# Perifericos_Schematic.net
KiCad netlist of a schematic drawn in Altium Designer
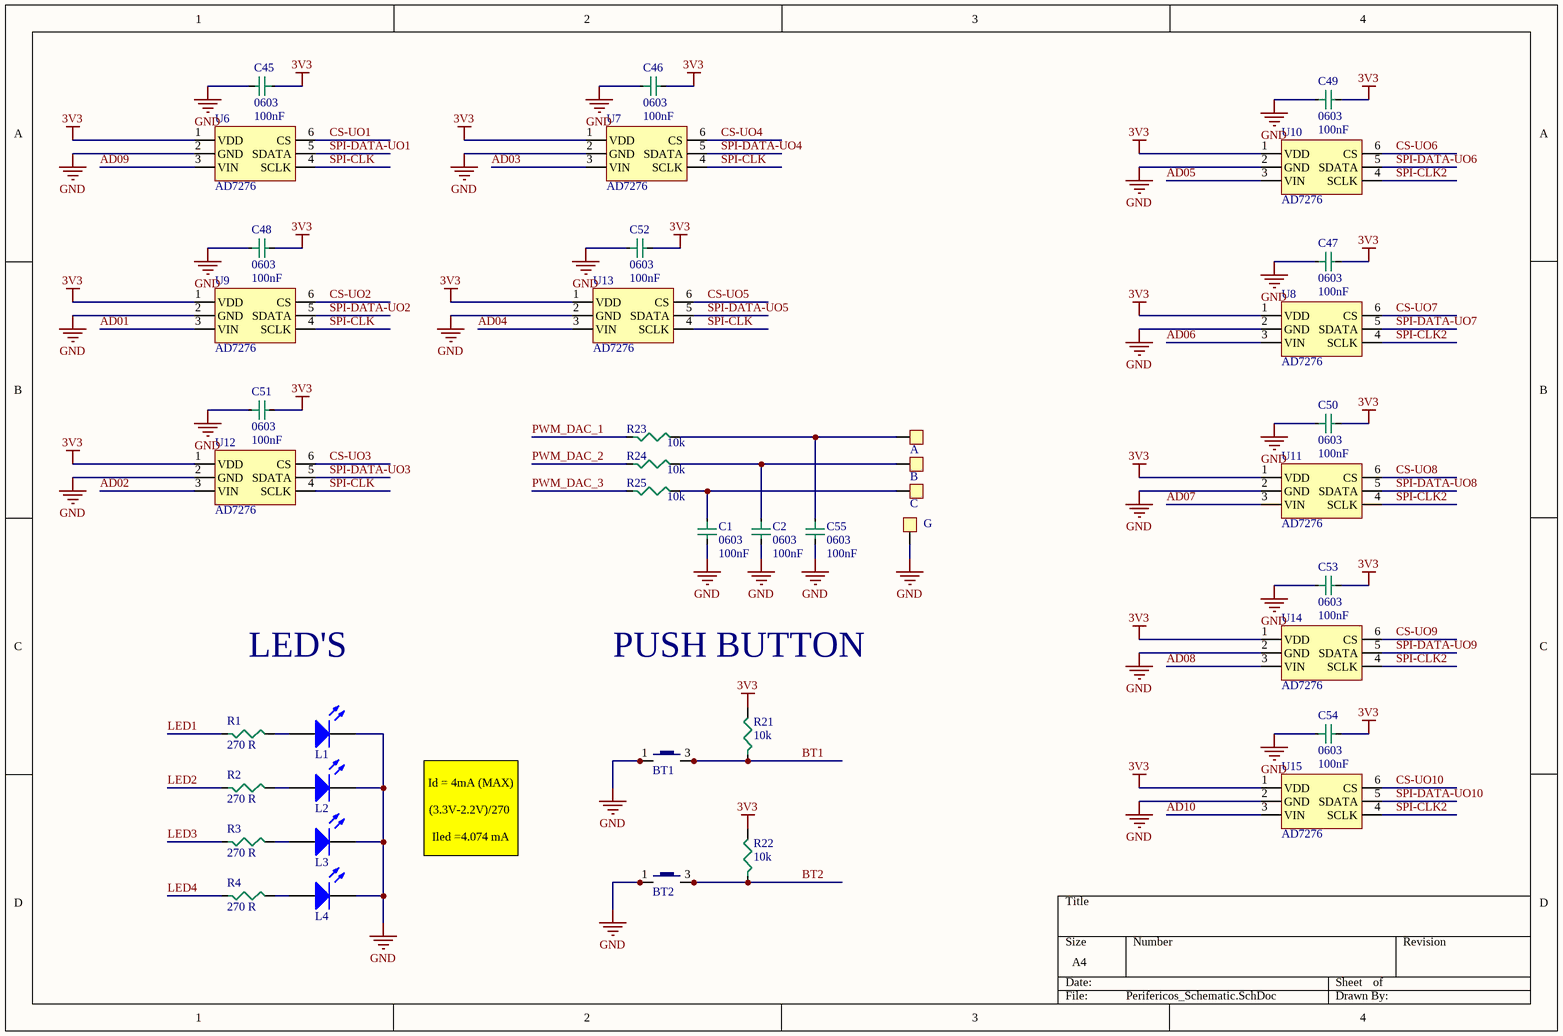
[diagram p0: Perifericos_Schematic.SchDoc]

(export (version "E")
  (design (tool "Eeschema 10.0.6"))
  (components
    (comp (ref "A")
      (value "TEST POINT PC MINI .040\"D, 0.010\" x 0.020\" (0.25mm x 0.51mm)")
      (footprint "PC test RED")
      (libsource (lib "") (part "Test Point Keystone_1"))
    )
    (comp (ref "B")
      (value "TEST POINT PC MINI .040\"D, 0.010\" x 0.020\" (0.25mm x 0.51mm)")
      (footprint "PC test GREEN")
      (libsource (lib "") (part "Test Point Keystone_1"))
    )
    (comp (ref "BT1")
      (value "BOTAO SMD_MENOR")
      (footprint "BOTAO SMD - MENOR")
      (description "SWITCH TACTILE SPST-NO 0.05A 32V")
      (libsource (lib "Schlib1") (part "BOTAO SMD_MENOR"))
    )
    (comp (ref "BT2")
      (value "BOTAO SMD_MENOR")
      (footprint "BOTAO SMD - MENOR")
      (description "SWITCH TACTILE SPST-NO 0.05A 32V")
      (libsource (lib "Schlib1") (part "BOTAO SMD_MENOR"))
    )
    (comp (ref "C")
      (value "TEST POINT PC MINI .040\"D, 0.010\" x 0.020\" (0.25mm x 0.51mm)")
      (footprint "PC test BLUE")
      (libsource (lib "") (part "Test Point Keystone_1"))
    )
    (comp (ref "C1")
      (value "0603")
      (footprint "0603C")
      (description "Capacitor SMD 0603")
      (fields (field (name "ALTIUM_VALUE") "100nF"))
      (libsource (lib "RLC_Integrated_Library") (part "Capacitor SMD 0603"))
    )
    (comp (ref "C2")
      (value "0603")
      (footprint "0603C")
      (description "Capacitor SMD 0603")
      (fields (field (name "ALTIUM_VALUE") "100nF"))
      (libsource (lib "RLC_Integrated_Library") (part "Capacitor SMD 0603"))
    )
    (comp (ref "C45")
      (value "0603")
      (footprint "0603C")
      (description "Capacitor SMD 0603")
      (fields (field (name "ALTIUM_VALUE") "100nF"))
      (libsource (lib "RLC_Integrated_Library") (part "Capacitor SMD 0603"))
    )
    (comp (ref "C46")
      (value "0603")
      (footprint "0603C")
      (description "Capacitor SMD 0603")
      (fields (field (name "ALTIUM_VALUE") "100nF"))
      (libsource (lib "RLC_Integrated_Library") (part "Capacitor SMD 0603"))
    )
    (comp (ref "C47")
      (value "0603")
      (footprint "0603C")
      (description "Capacitor SMD 0603")
      (fields (field (name "ALTIUM_VALUE") "100nF"))
      (libsource (lib "RLC_Integrated_Library") (part "Capacitor SMD 0603"))
    )
    (comp (ref "C48")
      (value "0603")
      (footprint "0603C")
      (description "Capacitor SMD 0603")
      (fields (field (name "ALTIUM_VALUE") "100nF"))
      (libsource (lib "RLC_Integrated_Library") (part "Capacitor SMD 0603"))
    )
    (comp (ref "C49")
      (value "0603")
      (footprint "0603C")
      (description "Capacitor SMD 0603")
      (fields (field (name "ALTIUM_VALUE") "100nF"))
      (libsource (lib "RLC_Integrated_Library") (part "Capacitor SMD 0603"))
    )
    (comp (ref "C50")
      (value "0603")
      (footprint "0603C")
      (description "Capacitor SMD 0603")
      (fields (field (name "ALTIUM_VALUE") "100nF"))
      (libsource (lib "RLC_Integrated_Library") (part "Capacitor SMD 0603"))
    )
    (comp (ref "C51")
      (value "0603")
      (footprint "0603C")
      (description "Capacitor SMD 0603")
      (fields (field (name "ALTIUM_VALUE") "100nF"))
      (libsource (lib "RLC_Integrated_Library") (part "Capacitor SMD 0603"))
    )
    (comp (ref "C52")
      (value "0603")
      (footprint "0603C")
      (description "Capacitor SMD 0603")
      (fields (field (name "ALTIUM_VALUE") "100nF"))
      (libsource (lib "RLC_Integrated_Library") (part "Capacitor SMD 0603"))
    )
    (comp (ref "C53")
      (value "0603")
      (footprint "0603C")
      (description "Capacitor SMD 0603")
      (fields (field (name "ALTIUM_VALUE") "100nF"))
      (libsource (lib "RLC_Integrated_Library") (part "Capacitor SMD 0603"))
    )
    (comp (ref "C54")
      (value "0603")
      (footprint "0603C")
      (description "Capacitor SMD 0603")
      (fields (field (name "ALTIUM_VALUE") "100nF"))
      (libsource (lib "RLC_Integrated_Library") (part "Capacitor SMD 0603"))
    )
    (comp (ref "C55")
      (value "0603")
      (footprint "0603C")
      (description "Capacitor SMD 0603")
      (fields (field (name "ALTIUM_VALUE") "100nF"))
      (libsource (lib "RLC_Integrated_Library") (part "Capacitor SMD 0603"))
    )
    (comp (ref "G")
      (value "TEST POINT PC MINI .040\"D, 0.010\" x 0.020\" (0.25mm x 0.51mm)")
      (footprint "PC test BLACK")
      (libsource (lib "Miscellaneous_Connectors_Integrated_Library") (part "Test Point Keystone"))
    )
    (comp (ref "L1")
      (value "LED 0603")
      (footprint "LED SMD 0603")
      (description "Typical INFRARED GaAs LED")
      (fields (field (name "PUBLISHER") "Altium Limited"))
      (libsource (lib "Diodo_Transistor_Integrated_Library") (part "LED 0603 SMD"))
    )
    (comp (ref "L2")
      (value "LED 0805")
      (footprint "LED SMD 0603")
      (description "Typical INFRARED GaAs LED")
      (fields (field (name "PUBLISHER") "Altium Limited"))
      (libsource (lib "Diodo_Transistor_Integrated_Library") (part "LED 0603 SMD"))
    )
    (comp (ref "L3")
      (value "LED 0805")
      (footprint "LED SMD 0603")
      (description "Typical INFRARED GaAs LED")
      (fields (field (name "PUBLISHER") "Altium Limited"))
      (libsource (lib "Diodo_Transistor_Integrated_Library") (part "LED 0603 SMD"))
    )
    (comp (ref "L4")
      (value "LED 0805")
      (footprint "LED SMD 0603")
      (description "Typical INFRARED GaAs LED")
      (fields (field (name "PUBLISHER") "Altium Limited"))
      (libsource (lib "Diodo_Transistor_Integrated_Library") (part "LED 0603 SMD"))
    )
    (comp (ref "R1")
      (value "270 R")
      (footprint "0603")
      (description "Resistor SMD 0603 1/10 W")
      (fields (field (name "Comment") "0603"))
      (libsource (lib "RLC_Integrated_Library") (part "Resistor SMD 0603 1/10 W"))
    )
    (comp (ref "R2")
      (value "270 R")
      (footprint "0603")
      (description "Resistor SMD 0603 1/10 W")
      (fields (field (name "Comment") "0805"))
      (libsource (lib "RLC_Integrated_Library") (part "Resistor SMD 0603 1/10 W"))
    )
    (comp (ref "R3")
      (value "270 R")
      (footprint "0603")
      (description "Resistor SMD 0603 1/10 W")
      (fields (field (name "Comment") "0805"))
      (libsource (lib "RLC_Integrated_Library") (part "Resistor SMD 0603 1/10 W"))
    )
    (comp (ref "R4")
      (value "270 R")
      (footprint "0603")
      (description "Resistor SMD 0603 1/10 W")
      (fields (field (name "Comment") "0805"))
      (libsource (lib "RLC_Integrated_Library") (part "Resistor SMD 0603 1/10 W"))
    )
    (comp (ref "R21")
      (value "10k")
      (footprint "0603")
      (description "Resistor SMD 0603 1/10 W")
      (fields (field (name "Comment") "0603"))
      (libsource (lib "RLC_Integrated_Library") (part "Resistor SMD 0603 1/10 W"))
    )
    (comp (ref "R22")
      (value "10k")
      (footprint "0603")
      (description "Resistor SMD 0603 1/10 W")
      (fields (field (name "Comment") "0603"))
      (libsource (lib "RLC_Integrated_Library") (part "Resistor SMD 0603 1/10 W"))
    )
    (comp (ref "R23")
      (value "10k")
      (footprint "0603")
      (description "Resistor SMD 0603 1/10 W")
      (fields (field (name "Comment") "0603"))
      (libsource (lib "RLC_Integrated_Library") (part "Resistor SMD 0603 1/10 W"))
    )
    (comp (ref "R24")
      (value "10k")
      (footprint "0603")
      (description "Resistor SMD 0603 1/10 W")
      (fields (field (name "Comment") "0603"))
      (libsource (lib "RLC_Integrated_Library") (part "Resistor SMD 0603 1/10 W"))
    )
    (comp (ref "R25")
      (value "10k")
      (footprint "0603")
      (description "Resistor SMD 0603 1/10 W")
      (fields (field (name "Comment") "0603"))
      (libsource (lib "RLC_Integrated_Library") (part "Resistor SMD 0603 1/10 W"))
    )
    (comp (ref "U6")
      (value "AD7276")
      (footprint "SOT23-6")
      (description "IC ADC 12BIT 3MSPS 6TSOT")
      (libsource (lib "Schlib1") (part "AD7276AUJZ-500RL7"))
    )
    (comp (ref "U7")
      (value "AD7276")
      (footprint "SOT23-6")
      (description "IC ADC 12BIT 3MSPS 6TSOT")
      (libsource (lib "Schlib1") (part "AD7276AUJZ-500RL7"))
    )
    (comp (ref "U8")
      (value "AD7276")
      (footprint "SOT23-6")
      (description "IC ADC 12BIT 3MSPS 6TSOT")
      (libsource (lib "Schlib1") (part "AD7276AUJZ-500RL7"))
    )
    (comp (ref "U9")
      (value "AD7276")
      (footprint "SOT23-6")
      (description "IC ADC 12BIT 3MSPS 6TSOT")
      (libsource (lib "Schlib1") (part "AD7276AUJZ-500RL7"))
    )
    (comp (ref "U10")
      (value "AD7276")
      (footprint "SOT23-6")
      (description "IC ADC 12BIT 3MSPS 6TSOT")
      (libsource (lib "Schlib1") (part "AD7276AUJZ-500RL7"))
    )
    (comp (ref "U11")
      (value "AD7276")
      (footprint "SOT23-6")
      (description "IC ADC 12BIT 3MSPS 6TSOT")
      (libsource (lib "Schlib1") (part "AD7276AUJZ-500RL7"))
    )
    (comp (ref "U12")
      (value "AD7276")
      (footprint "SOT23-6")
      (description "IC ADC 12BIT 3MSPS 6TSOT")
      (libsource (lib "Schlib1") (part "AD7276AUJZ-500RL7"))
    )
    (comp (ref "U13")
      (value "AD7276")
      (footprint "SOT23-6")
      (description "IC ADC 12BIT 3MSPS 6TSOT")
      (libsource (lib "Schlib1") (part "AD7276AUJZ-500RL7"))
    )
    (comp (ref "U14")
      (value "AD7276")
      (footprint "SOT23-6")
      (description "IC ADC 12BIT 3MSPS 6TSOT")
      (libsource (lib "Schlib1") (part "AD7276AUJZ-500RL7"))
    )
    (comp (ref "U15")
      (value "AD7276")
      (footprint "SOT23-6")
      (description "IC ADC 12BIT 3MSPS 6TSOT")
      (libsource (lib "Schlib1") (part "AD7276AUJZ-500RL7"))
    )
  )
  (nets
    (net (code "1") (name "/AD01") (class "Default")
      (node (ref "U9") (pin "3") (pinfunction "VIN_3") (pintype "passive"))
    )
    (net (code "2") (name "/AD02") (class "Default")
      (node (ref "U12") (pin "3") (pinfunction "VIN_3") (pintype "passive"))
    )
    (net (code "3") (name "/AD03") (class "Default")
      (node (ref "U7") (pin "3") (pinfunction "VIN_3") (pintype "passive"))
    )
    (net (code "4") (name "/AD04") (class "Default")
      (node (ref "U13") (pin "3") (pinfunction "VIN_3") (pintype "passive"))
    )
    (net (code "5") (name "/AD05") (class "Default")
      (node (ref "U10") (pin "3") (pinfunction "VIN_3") (pintype "passive"))
    )
    (net (code "6") (name "/AD06") (class "Default")
      (node (ref "U8") (pin "3") (pinfunction "VIN_3") (pintype "passive"))
    )
    (net (code "7") (name "/AD07") (class "Default")
      (node (ref "U11") (pin "3") (pinfunction "VIN_3") (pintype "passive"))
    )
    (net (code "8") (name "/AD08") (class "Default")
      (node (ref "U14") (pin "3") (pinfunction "VIN_3") (pintype "passive"))
    )
    (net (code "9") (name "/AD09") (class "Default")
      (node (ref "U6") (pin "3") (pinfunction "VIN_3") (pintype "passive"))
    )
    (net (code "10") (name "/AD10") (class "Default")
      (node (ref "U15") (pin "3") (pinfunction "VIN_3") (pintype "passive"))
    )
    (net (code "11") (name "/BT1") (class "Default")
      (node (ref "BT1") (pin "3") (pinfunction "3_3") (pintype "passive"))
      (node (ref "BT1") (pin "4") (pinfunction "4_4") (pintype "passive"))
      (node (ref "R21") (pin "1") (pinfunction "1_1") (pintype "passive"))
    )
    (net (code "12") (name "/BT2") (class "Default")
      (node (ref "BT2") (pin "3") (pinfunction "3_3") (pintype "passive"))
      (node (ref "BT2") (pin "4") (pinfunction "4_4") (pintype "passive"))
      (node (ref "R22") (pin "1") (pinfunction "1_1") (pintype "passive"))
    )
    (net (code "13") (name "/CS-UO1") (class "Default")
      (node (ref "U6") (pin "6") (pinfunction "CS_6") (pintype "passive"))
    )
    (net (code "14") (name "/CS-UO2") (class "Default")
      (node (ref "U9") (pin "6") (pinfunction "CS_6") (pintype "passive"))
    )
    (net (code "15") (name "/CS-UO3") (class "Default")
      (node (ref "U12") (pin "6") (pinfunction "CS_6") (pintype "passive"))
    )
    (net (code "16") (name "/CS-UO4") (class "Default")
      (node (ref "U7") (pin "6") (pinfunction "CS_6") (pintype "passive"))
    )
    (net (code "17") (name "/CS-UO5") (class "Default")
      (node (ref "U13") (pin "6") (pinfunction "CS_6") (pintype "passive"))
    )
    (net (code "18") (name "/CS-UO6") (class "Default")
      (node (ref "U10") (pin "6") (pinfunction "CS_6") (pintype "passive"))
    )
    (net (code "19") (name "/CS-UO7") (class "Default")
      (node (ref "U8") (pin "6") (pinfunction "CS_6") (pintype "passive"))
    )
    (net (code "20") (name "/CS-UO8") (class "Default")
      (node (ref "U11") (pin "6") (pinfunction "CS_6") (pintype "passive"))
    )
    (net (code "21") (name "/CS-UO9") (class "Default")
      (node (ref "U14") (pin "6") (pinfunction "CS_6") (pintype "passive"))
    )
    (net (code "22") (name "/CS-UO10") (class "Default")
      (node (ref "U15") (pin "6") (pinfunction "CS_6") (pintype "passive"))
    )
    (net (code "23") (name "/LED1") (class "Default")
      (node (ref "R1") (pin "1") (pinfunction "1_1") (pintype "passive"))
    )
    (net (code "24") (name "/LED2") (class "Default")
      (node (ref "R2") (pin "1") (pinfunction "1_1") (pintype "passive"))
    )
    (net (code "25") (name "/LED3") (class "Default")
      (node (ref "R3") (pin "1") (pinfunction "1_1") (pintype "passive"))
    )
    (net (code "26") (name "/LED4") (class "Default")
      (node (ref "R4") (pin "1") (pinfunction "1_1") (pintype "passive"))
    )
    (net (code "27") (name "/PWM_DAC_1") (class "Default")
      (node (ref "R23") (pin "1") (pinfunction "1_1") (pintype "passive"))
    )
    (net (code "28") (name "/PWM_DAC_2") (class "Default")
      (node (ref "R24") (pin "1") (pinfunction "1_1") (pintype "passive"))
    )
    (net (code "29") (name "/PWM_DAC_3") (class "Default")
      (node (ref "R25") (pin "1") (pinfunction "1_1") (pintype "passive"))
    )
    (net (code "30") (name "/SPI-CLK") (class "Default")
      (node (ref "U12") (pin "4") (pinfunction "SCLK_4") (pintype "passive"))
      (node (ref "U13") (pin "4") (pinfunction "SCLK_4") (pintype "passive"))
      (node (ref "U6") (pin "4") (pinfunction "SCLK_4") (pintype "passive"))
      (node (ref "U7") (pin "4") (pinfunction "SCLK_4") (pintype "passive"))
      (node (ref "U9") (pin "4") (pinfunction "SCLK_4") (pintype "passive"))
    )
    (net (code "31") (name "/SPI-CLK2") (class "Default")
      (node (ref "U10") (pin "4") (pinfunction "SCLK_4") (pintype "passive"))
      (node (ref "U11") (pin "4") (pinfunction "SCLK_4") (pintype "passive"))
      (node (ref "U14") (pin "4") (pinfunction "SCLK_4") (pintype "passive"))
      (node (ref "U15") (pin "4") (pinfunction "SCLK_4") (pintype "passive"))
      (node (ref "U8") (pin "4") (pinfunction "SCLK_4") (pintype "passive"))
    )
    (net (code "32") (name "/SPI-DATA-UO1") (class "Default")
      (node (ref "U6") (pin "5") (pinfunction "SDATA_5") (pintype "passive"))
    )
    (net (code "33") (name "/SPI-DATA-UO2") (class "Default")
      (node (ref "U9") (pin "5") (pinfunction "SDATA_5") (pintype "passive"))
    )
    (net (code "34") (name "/SPI-DATA-UO3") (class "Default")
      (node (ref "U12") (pin "5") (pinfunction "SDATA_5") (pintype "passive"))
    )
    (net (code "35") (name "/SPI-DATA-UO4") (class "Default")
      (node (ref "U7") (pin "5") (pinfunction "SDATA_5") (pintype "passive"))
    )
    (net (code "36") (name "/SPI-DATA-UO5") (class "Default")
      (node (ref "U13") (pin "5") (pinfunction "SDATA_5") (pintype "passive"))
    )
    (net (code "37") (name "/SPI-DATA-UO6") (class "Default")
      (node (ref "U10") (pin "5") (pinfunction "SDATA_5") (pintype "passive"))
    )
    (net (code "38") (name "/SPI-DATA-UO7") (class "Default")
      (node (ref "U8") (pin "5") (pinfunction "SDATA_5") (pintype "passive"))
    )
    (net (code "39") (name "/SPI-DATA-UO8") (class "Default")
      (node (ref "U11") (pin "5") (pinfunction "SDATA_5") (pintype "passive"))
    )
    (net (code "40") (name "/SPI-DATA-UO9") (class "Default")
      (node (ref "U14") (pin "5") (pinfunction "SDATA_5") (pintype "passive"))
    )
    (net (code "41") (name "/SPI-DATA-UO10") (class "Default")
      (node (ref "U15") (pin "5") (pinfunction "SDATA_5") (pintype "passive"))
    )
    (net (code "42") (name "3V3") (class "Default")
      (node (ref "C45") (pin "1") (pinfunction "1_1") (pintype "passive"))
      (node (ref "C46") (pin "2") (pinfunction "2_2") (pintype "passive"))
      (node (ref "C47") (pin "2") (pinfunction "2_2") (pintype "passive"))
      (node (ref "C48") (pin "2") (pinfunction "2_2") (pintype "passive"))
      (node (ref "C49") (pin "2") (pinfunction "2_2") (pintype "passive"))
      (node (ref "C50") (pin "2") (pinfunction "2_2") (pintype "passive"))
      (node (ref "C51") (pin "2") (pinfunction "2_2") (pintype "passive"))
      (node (ref "C52") (pin "2") (pinfunction "2_2") (pintype "passive"))
      (node (ref "C53") (pin "2") (pinfunction "2_2") (pintype "passive"))
      (node (ref "C54") (pin "2") (pinfunction "2_2") (pintype "passive"))
      (node (ref "R21") (pin "2") (pinfunction "2_2") (pintype "passive"))
      (node (ref "R22") (pin "2") (pinfunction "2_2") (pintype "passive"))
      (node (ref "U10") (pin "1") (pinfunction "VDD_1") (pintype "passive"))
      (node (ref "U11") (pin "1") (pinfunction "VDD_1") (pintype "passive"))
      (node (ref "U12") (pin "1") (pinfunction "VDD_1") (pintype "passive"))
      (node (ref "U13") (pin "1") (pinfunction "VDD_1") (pintype "passive"))
      (node (ref "U14") (pin "1") (pinfunction "VDD_1") (pintype "passive"))
      (node (ref "U15") (pin "1") (pinfunction "VDD_1") (pintype "passive"))
      (node (ref "U6") (pin "1") (pinfunction "VDD_1") (pintype "passive"))
      (node (ref "U7") (pin "1") (pinfunction "VDD_1") (pintype "passive"))
      (node (ref "U8") (pin "1") (pinfunction "VDD_1") (pintype "passive"))
      (node (ref "U9") (pin "1") (pinfunction "VDD_1") (pintype "passive"))
    )
    (net (code "43") (name "GND") (class "Default")
      (node (ref "BT1") (pin "1") (pinfunction "1_1") (pintype "passive"))
      (node (ref "BT1") (pin "2") (pinfunction "2_2") (pintype "passive"))
      (node (ref "BT2") (pin "1") (pinfunction "1_1") (pintype "passive"))
      (node (ref "BT2") (pin "2") (pinfunction "2_2") (pintype "passive"))
      (node (ref "C1") (pin "2") (pinfunction "2_2") (pintype "passive"))
      (node (ref "C2") (pin "2") (pinfunction "2_2") (pintype "passive"))
      (node (ref "C45") (pin "2") (pinfunction "2_2") (pintype "passive"))
      (node (ref "C46") (pin "1") (pinfunction "1_1") (pintype "passive"))
      (node (ref "C47") (pin "1") (pinfunction "1_1") (pintype "passive"))
      (node (ref "C48") (pin "1") (pinfunction "1_1") (pintype "passive"))
      (node (ref "C49") (pin "1") (pinfunction "1_1") (pintype "passive"))
      (node (ref "C50") (pin "1") (pinfunction "1_1") (pintype "passive"))
      (node (ref "C51") (pin "1") (pinfunction "1_1") (pintype "passive"))
      (node (ref "C52") (pin "1") (pinfunction "1_1") (pintype "passive"))
      (node (ref "C53") (pin "1") (pinfunction "1_1") (pintype "passive"))
      (node (ref "C54") (pin "1") (pinfunction "1_1") (pintype "passive"))
      (node (ref "C55") (pin "2") (pinfunction "2_2") (pintype "passive"))
      (node (ref "G") (pin "1") (pinfunction "1_1") (pintype "passive"))
      (node (ref "L1") (pin "2") (pinfunction "K_2") (pintype "passive"))
      (node (ref "L2") (pin "2") (pinfunction "K_2") (pintype "passive"))
      (node (ref "L3") (pin "2") (pinfunction "K_2") (pintype "passive"))
      (node (ref "L4") (pin "2") (pinfunction "K_2") (pintype "passive"))
      (node (ref "U10") (pin "2") (pinfunction "GND_2") (pintype "passive"))
      (node (ref "U11") (pin "2") (pinfunction "GND_2") (pintype "passive"))
      (node (ref "U12") (pin "2") (pinfunction "GND_2") (pintype "passive"))
      (node (ref "U13") (pin "2") (pinfunction "GND_2") (pintype "passive"))
      (node (ref "U14") (pin "2") (pinfunction "GND_2") (pintype "passive"))
      (node (ref "U15") (pin "2") (pinfunction "GND_2") (pintype "passive"))
      (node (ref "U6") (pin "2") (pinfunction "GND_2") (pintype "passive"))
      (node (ref "U7") (pin "2") (pinfunction "GND_2") (pintype "passive"))
      (node (ref "U8") (pin "2") (pinfunction "GND_2") (pintype "passive"))
      (node (ref "U9") (pin "2") (pinfunction "GND_2") (pintype "passive"))
    )
    (net (code "44") (name "Net-(A-Pad1)") (class "Default")
      (node (ref "A") (pin "1") (pinfunction "1_1") (pintype "passive"))
      (node (ref "C55") (pin "1") (pinfunction "1_1") (pintype "passive"))
      (node (ref "R23") (pin "2") (pinfunction "2_2") (pintype "passive"))
    )
    (net (code "45") (name "Net-(B-Pad1)") (class "Default")
      (node (ref "B") (pin "1") (pinfunction "1_1") (pintype "passive"))
      (node (ref "C2") (pin "1") (pinfunction "1_1") (pintype "passive"))
      (node (ref "R24") (pin "2") (pinfunction "2_2") (pintype "passive"))
    )
    (net (code "46") (name "Net-(C-Pad1)") (class "Default")
      (node (ref "C") (pin "1") (pinfunction "1_1") (pintype "passive"))
      (node (ref "C1") (pin "1") (pinfunction "1_1") (pintype "passive"))
      (node (ref "R25") (pin "2") (pinfunction "2_2") (pintype "passive"))
    )
    (net (code "47") (name "Net-(L1-A)") (class "Default")
      (node (ref "L1") (pin "1") (pinfunction "A_1") (pintype "passive"))
      (node (ref "R1") (pin "2") (pinfunction "2_2") (pintype "passive"))
    )
    (net (code "48") (name "Net-(L2-A)") (class "Default")
      (node (ref "L2") (pin "1") (pinfunction "A_1") (pintype "passive"))
      (node (ref "R2") (pin "2") (pinfunction "2_2") (pintype "passive"))
    )
    (net (code "49") (name "Net-(L3-A)") (class "Default")
      (node (ref "L3") (pin "1") (pinfunction "A_1") (pintype "passive"))
      (node (ref "R3") (pin "2") (pinfunction "2_2") (pintype "passive"))
    )
    (net (code "50") (name "Net-(L4-A)") (class "Default")
      (node (ref "L4") (pin "1") (pinfunction "A_1") (pintype "passive"))
      (node (ref "R4") (pin "2") (pinfunction "2_2") (pintype "passive"))
    )
  )
)
